# VCAPC_panel.net
KiCad netlist of a schematic drawn in EAGLE
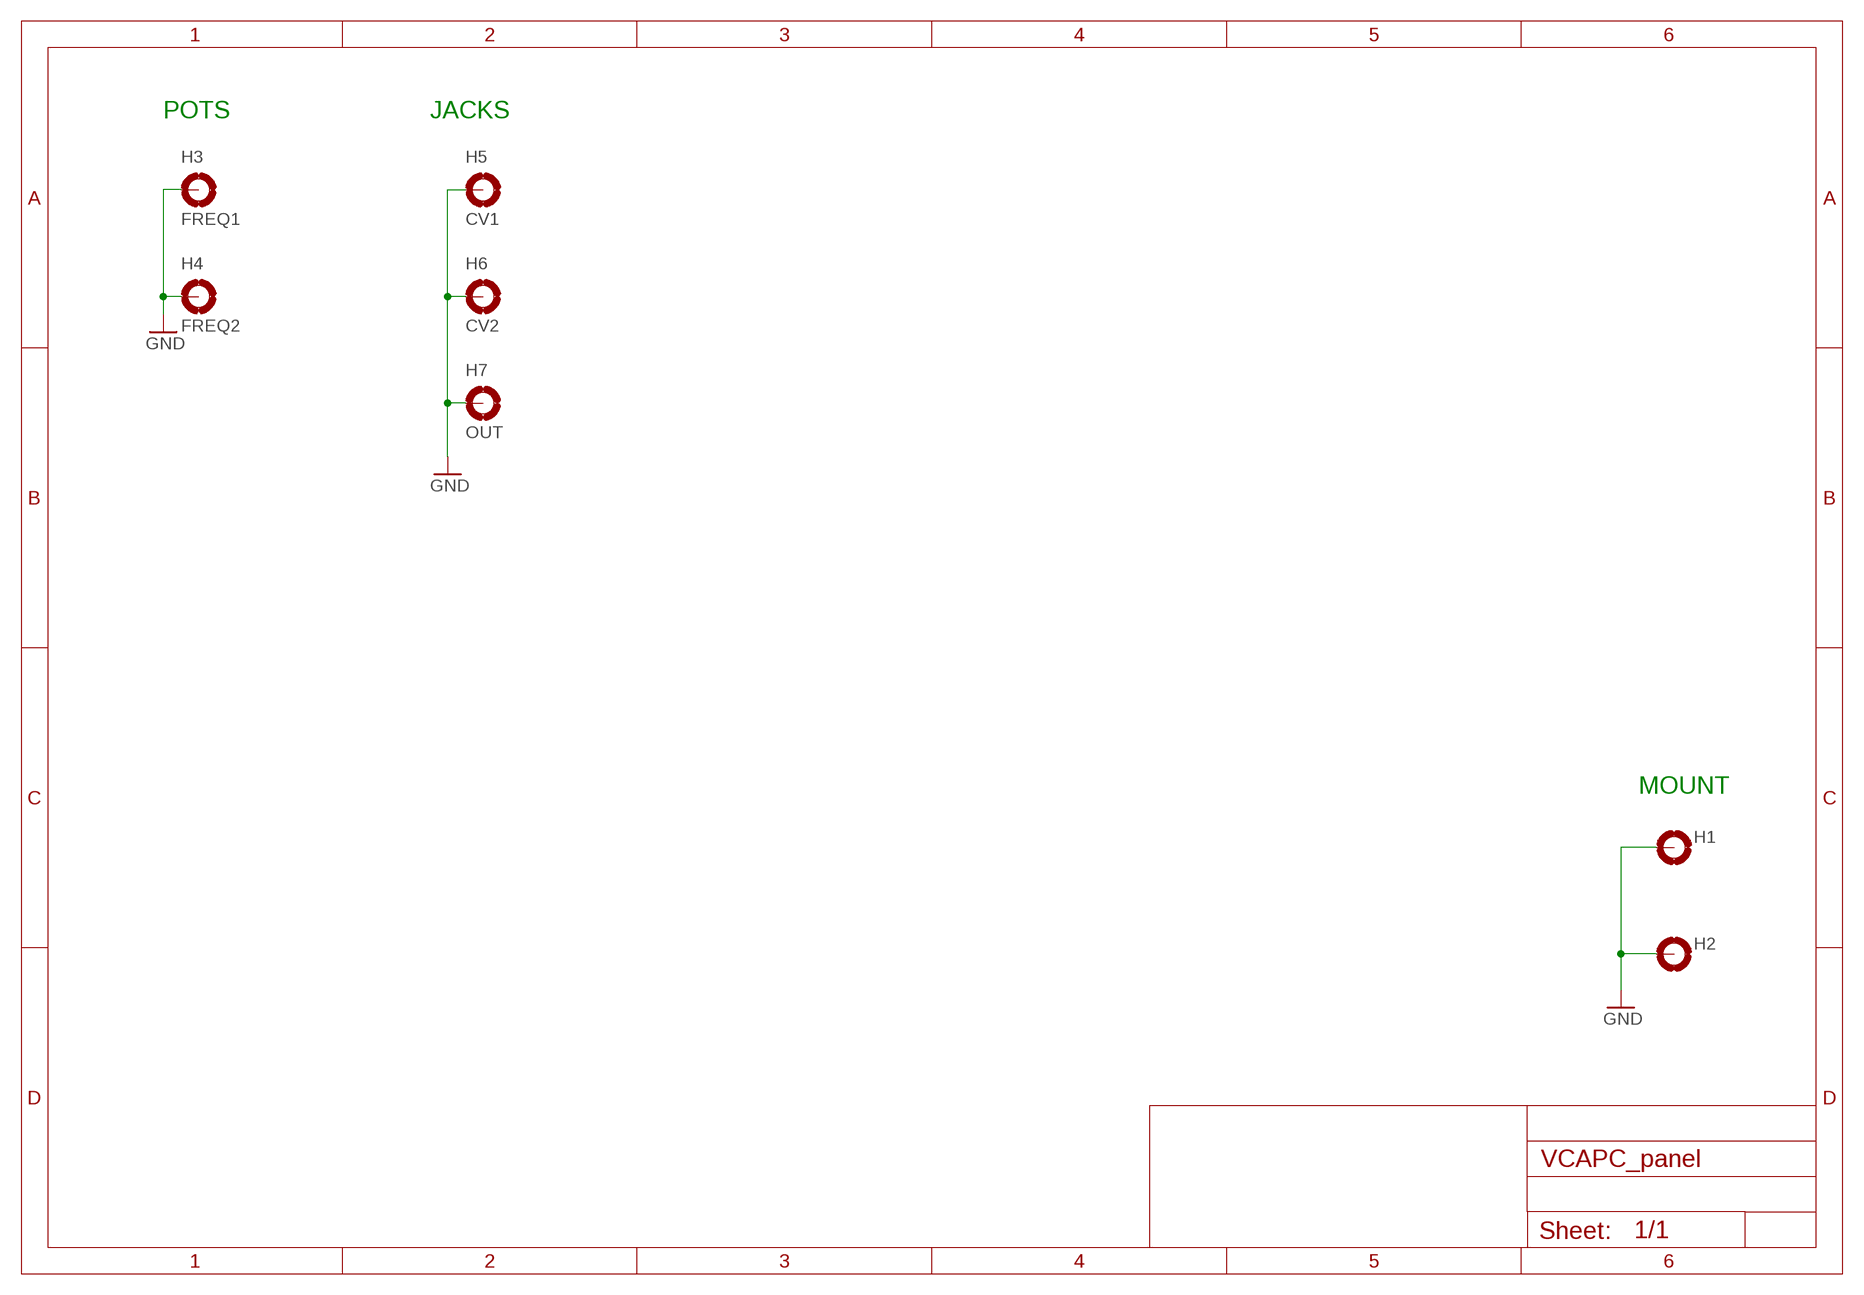
[diagram p0: schematic, sheet 1]

(export (version "E")
  (design (tool "Eeschema 10.0.6"))
  (components
    (comp (ref "H1")
      (value "MOUNT-PAD-LONG3.2")
      (footprint "eagle-import:3,2-PAD_L")
      (libsource (lib "eagle-import") (part "MOUNT-PAD-LONG3.2"))
    )
    (comp (ref "H2")
      (value "MOUNT-PAD-LONG3.2")
      (footprint "eagle-import:3,2-PAD_L")
      (libsource (lib "eagle-import") (part "MOUNT-PAD-LONG3.2"))
    )
    (comp (ref "H3")
      (value "FREQ1")
      (footprint "eagle-import:POT_WITH_SCALE")
      (libsource (lib "eagle-import") (part "MOUNT-PAD-ROUNDPOT1"))
    )
    (comp (ref "H4")
      (value "FREQ2")
      (footprint "eagle-import:POT_WITH_SCALE")
      (libsource (lib "eagle-import") (part "MOUNT-PAD-ROUNDPOT1"))
    )
    (comp (ref "H5")
      (value "CV1")
      (footprint "eagle-import:PAD_JACK")
      (libsource (lib "eagle-import") (part "MOUNT-PAD-ROUNDJACK"))
    )
    (comp (ref "H6")
      (value "CV2")
      (footprint "eagle-import:PAD_JACK")
      (libsource (lib "eagle-import") (part "MOUNT-PAD-ROUNDJACK"))
    )
    (comp (ref "H7")
      (value "OUT")
      (footprint "eagle-import:PAD_JACK")
      (libsource (lib "eagle-import") (part "MOUNT-PAD-ROUNDJACK"))
    )
  )
  (nets
    (net (code "1") (name "GND") (class "Default")
      (node (ref "H1") (pin "B3,2") (pinfunction "MOUNT_B3,2") (pintype "passive"))
      (node (ref "H2") (pin "B3,2") (pinfunction "MOUNT_B3,2") (pintype "passive"))
      (node (ref "H3") (pin "1") (pinfunction "MOUNT_1") (pintype "passive"))
      (node (ref "H4") (pin "1") (pinfunction "MOUNT_1") (pintype "passive"))
      (node (ref "H5") (pin "B6,223") (pinfunction "MOUNT_B6,223") (pintype "passive"))
      (node (ref "H6") (pin "B6,223") (pinfunction "MOUNT_B6,223") (pintype "passive"))
      (node (ref "H7") (pin "B6,223") (pinfunction "MOUNT_B6,223") (pintype "passive"))
    )
  )
)
